# SWD.net
KiCad netlist of a schematic drawn in Altium Designer
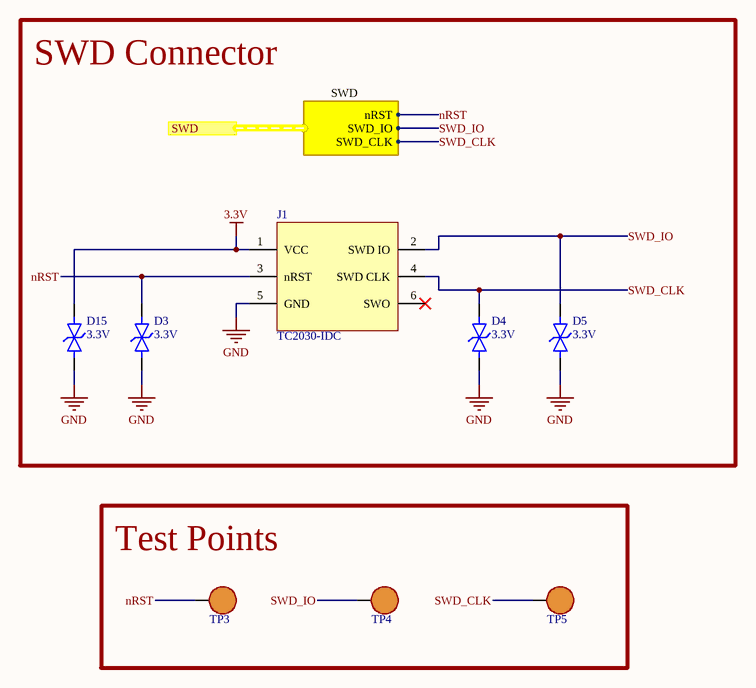
[diagram p0: SWD.SchDoc]

(export (version "E")
  (design (tool "Eeschema 10.0.6"))
  (components
    (comp (ref "D3")
      (value "DESD3V3E1BL-7B")
      (footprint "Christmas-2024_TSO-PCB:0402-TVS")
      (description "TVS DIODE 3.3VWM 7VC DFN1006-2")
      (fields (field (name "MFR") "Diodes Incorporated") (field (name "VRS") "3.3V"))
      (libsource (lib "Christmas-2024_TSO-PCB") (part "TVS Diode 3.3V Bi"))
    )
    (comp (ref "D4")
      (value "DESD3V3E1BL-7B")
      (footprint "Christmas-2024_TSO-PCB:0402-TVS")
      (description "TVS DIODE 3.3VWM 7VC DFN1006-2")
      (fields (field (name "MFR") "Diodes Incorporated") (field (name "VRS") "3.3V"))
      (libsource (lib "Christmas-2024_TSO-PCB") (part "TVS Diode 3.3V Bi"))
    )
    (comp (ref "D5")
      (value "DESD3V3E1BL-7B")
      (footprint "Christmas-2024_TSO-PCB:0402-TVS")
      (description "TVS DIODE 3.3VWM 7VC DFN1006-2")
      (fields (field (name "MFR") "Diodes Incorporated") (field (name "VRS") "3.3V"))
      (libsource (lib "Christmas-2024_TSO-PCB") (part "TVS Diode 3.3V Bi"))
    )
    (comp (ref "D15")
      (value "DESD3V3E1BL-7B")
      (footprint "Christmas-2024_TSO-PCB:0402-TVS")
      (description "TVS DIODE 3.3VWM 7VC DFN1006-2")
      (fields (field (name "MFR") "Diodes Incorporated") (field (name "VRS") "3.3V"))
      (libsource (lib "Christmas-2024_TSO-PCB") (part "TVS Diode 3.3V Bi"))
    )
    (comp (ref "J1")
      (value "TC2030-IDC")
      (footprint "Christmas-2024_TSO-PCB:TAG CONNECT TC2030IDC - NO 3D MODEL")
      (description "\"Plug of Nails\" POGO Pin connector")
      (fields (field (name "MFR") "Tag-Connect"))
      (libsource (lib "Christmas-2024_TSO-PCB") (part "TC2030-IDC"))
    )
    (comp (ref "TP3")
      (value "RCWCTE")
      (footprint "Christmas-2024_TSO-PCB:RCWCTE")
      (description "Test Point, Surface Mount")
      (fields (field (name "MFR") "KOA Speer Electronics, Inc."))
      (libsource (lib "Christmas-2024_TSO-PCB") (part "TEST POINT"))
    )
    (comp (ref "TP4")
      (value "RCWCTE")
      (footprint "Christmas-2024_TSO-PCB:RCWCTE")
      (description "Test Point, Surface Mount")
      (fields (field (name "MFR") "KOA Speer Electronics, Inc."))
      (libsource (lib "Christmas-2024_TSO-PCB") (part "TEST POINT"))
    )
    (comp (ref "TP5")
      (value "RCWCTE")
      (footprint "Christmas-2024_TSO-PCB:RCWCTE")
      (description "Test Point, Surface Mount")
      (fields (field (name "MFR") "KOA Speer Electronics, Inc."))
      (libsource (lib "Christmas-2024_TSO-PCB") (part "TEST POINT"))
    )
  )
  (nets
    (net (code "2") (name "/SWD_CLK") (class "Default")
      (node (ref "D4") (pin "1") (pinfunction "1_1") (pintype "passive"))
      (node (ref "J1") (pin "4") (pinfunction "SWD_CLK_4") (pintype "passive"))
      (node (ref "TP5") (pin "1") (pinfunction "0_1") (pintype "passive"))
    )
    (net (code "3") (name "/SWD_IO") (class "Default")
      (node (ref "D5") (pin "1") (pinfunction "1_1") (pintype "passive"))
      (node (ref "J1") (pin "2") (pinfunction "SWD_IO_2") (pintype "passive"))
      (node (ref "TP4") (pin "1") (pinfunction "0_1") (pintype "passive"))
    )
    (net (code "4") (name "/nRST") (class "Default")
      (node (ref "D3") (pin "1") (pinfunction "1_1") (pintype "passive"))
      (node (ref "J1") (pin "3") (pinfunction "nRST_3") (pintype "passive"))
      (node (ref "TP3") (pin "1") (pinfunction "0_1") (pintype "passive"))
    )
    (net (code "6") (name "3.3V") (class "Default")
      (node (ref "D15") (pin "1") (pinfunction "1_1") (pintype "passive"))
      (node (ref "J1") (pin "1") (pinfunction "VCC_1") (pintype "passive"))
    )
    (net (code "7") (name "GND") (class "Default")
      (node (ref "D15") (pin "2") (pinfunction "2_2") (pintype "passive"))
      (node (ref "D3") (pin "2") (pinfunction "2_2") (pintype "passive"))
      (node (ref "D4") (pin "2") (pinfunction "2_2") (pintype "passive"))
      (node (ref "D5") (pin "2") (pinfunction "2_2") (pintype "passive"))
      (node (ref "J1") (pin "5") (pinfunction "GND_5") (pintype "passive"))
    )
    (net (code "8") (name "unconnected-(J1-SWO-Pad6)") (class "Default")
      (node (ref "J1") (pin "6") (pinfunction "SWO_6") (pintype "passive+no_connect"))
    )
  )
)
